# left_revision1_1.net
KiCad netlist of a schematic drawn in EAGLE
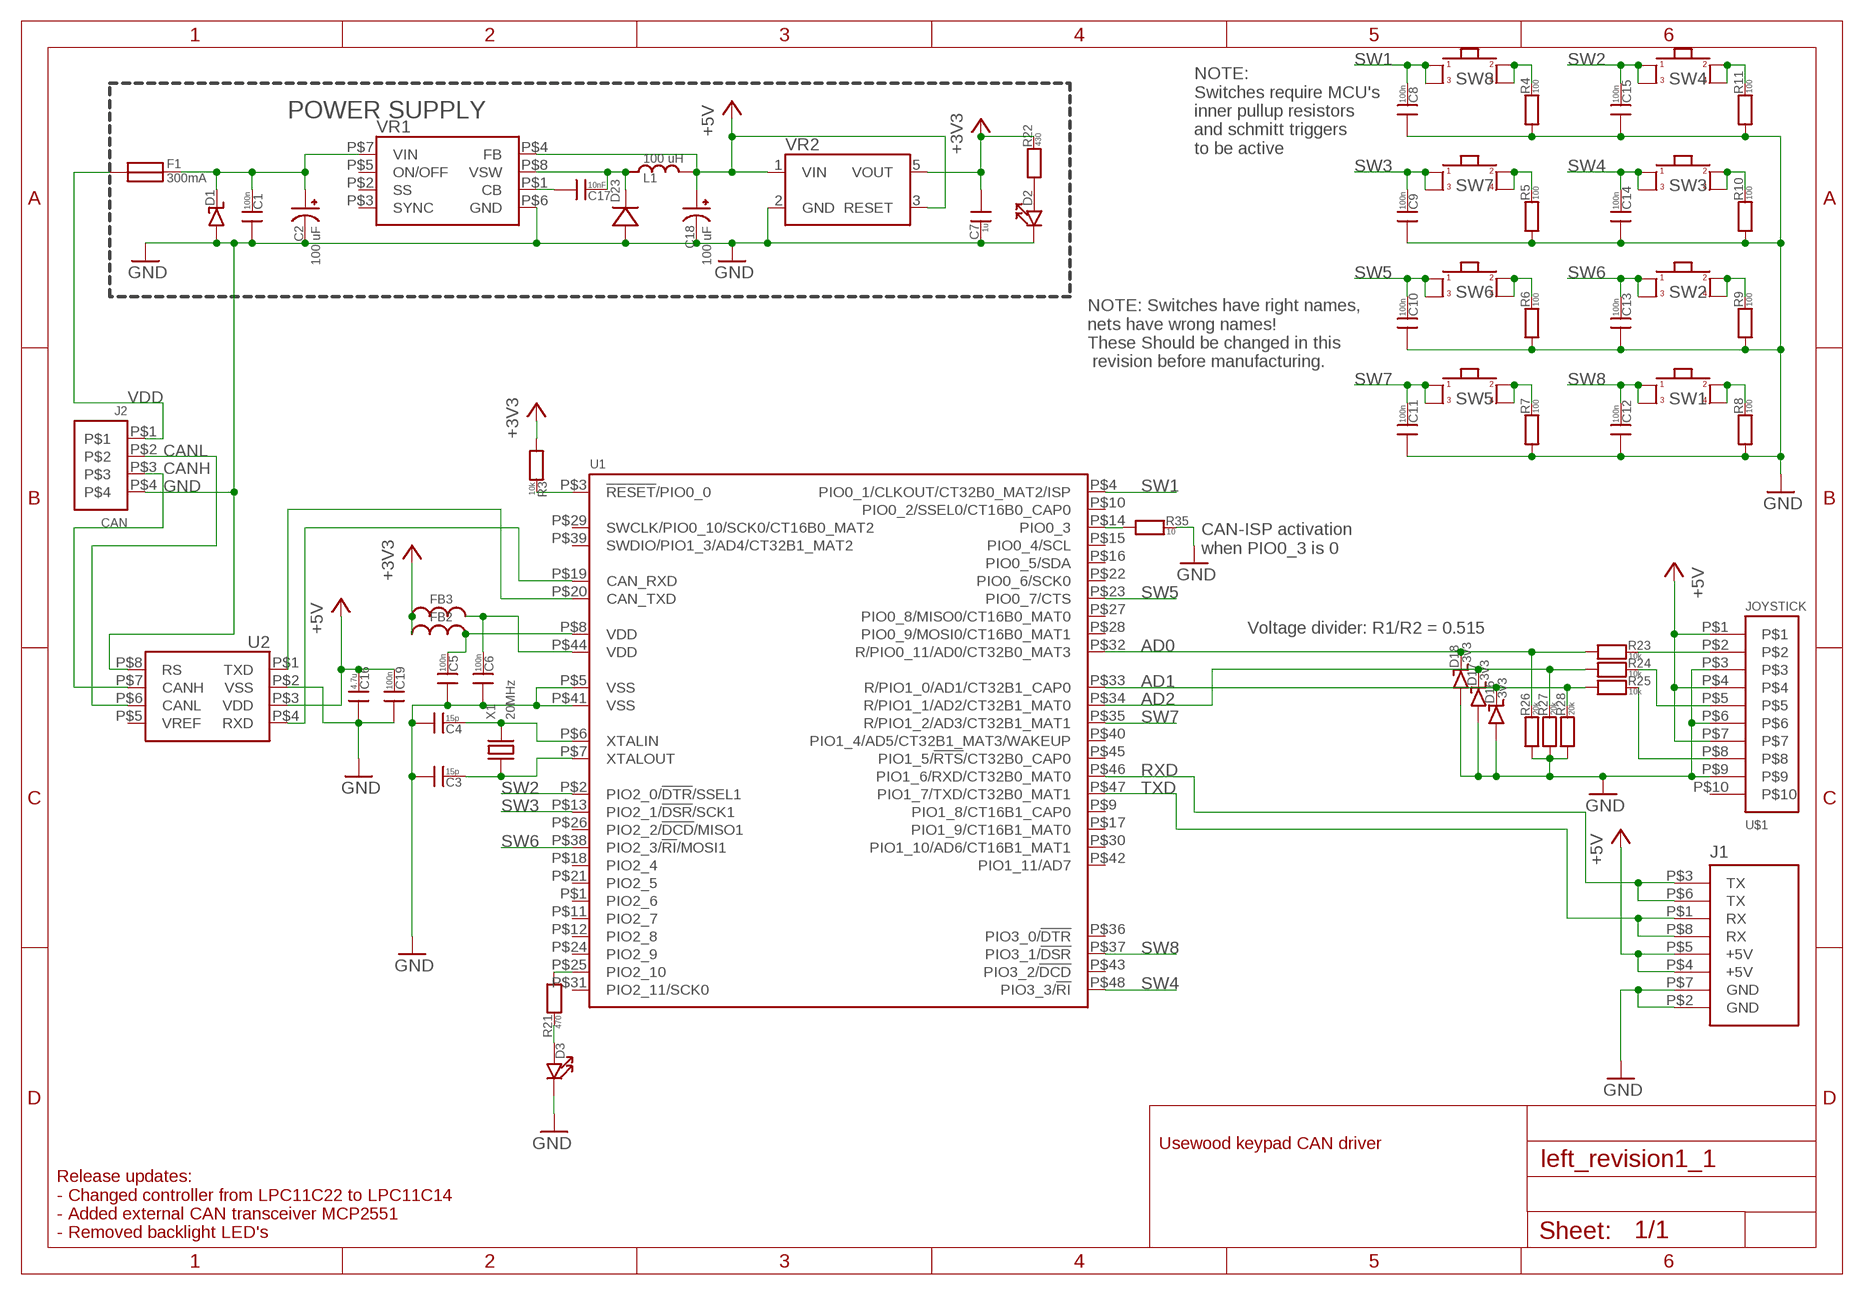
[diagram p0: schematic, sheet 1]

(export (version "E")
  (design (tool "Eeschema 10.0.6"))
  (components
    (comp (ref "C1")
      (value "100n")
      (footprint "eagle-import:0603_SILKSCREEN")
      (libsource (lib "eagle-import") (part "CAP0603_SILKSCREEN"))
    )
    (comp (ref "C2")
      (value "100 uF")
      (footprint "eagle-import:CAP_POL_SMD_10X10X10MM")
      (libsource (lib "eagle-import") (part "CAP_POLSMD_10X10X10MM"))
    )
    (comp (ref "C3")
      (value "15p")
      (footprint "eagle-import:0603_SILKSCREEN")
      (libsource (lib "eagle-import") (part "CAP0603_SILKSCREEN"))
    )
    (comp (ref "C4")
      (value "15p")
      (footprint "eagle-import:0603_SILKSCREEN")
      (libsource (lib "eagle-import") (part "CAP0603_SILKSCREEN"))
    )
    (comp (ref "C5")
      (value "100n")
      (footprint "eagle-import:0603_SILKSCREEN")
      (libsource (lib "eagle-import") (part "CAP0603_SILKSCREEN"))
    )
    (comp (ref "C6")
      (value "100n")
      (footprint "eagle-import:0603_SILKSCREEN")
      (libsource (lib "eagle-import") (part "CAP0603_SILKSCREEN"))
    )
    (comp (ref "C7")
      (value "1u")
      (footprint "eagle-import:0603_SILKSCREEN")
      (libsource (lib "eagle-import") (part "CAP0603_SILKSCREEN"))
    )
    (comp (ref "C8")
      (value "100n")
      (footprint "eagle-import:0603_SILKSCREEN")
      (libsource (lib "eagle-import") (part "CAP0603_SILKSCREEN"))
    )
    (comp (ref "C9")
      (value "100n")
      (footprint "eagle-import:0603_SILKSCREEN")
      (libsource (lib "eagle-import") (part "CAP0603_SILKSCREEN"))
    )
    (comp (ref "C10")
      (value "100n")
      (footprint "eagle-import:0603_SILKSCREEN")
      (libsource (lib "eagle-import") (part "CAP0603_SILKSCREEN"))
    )
    (comp (ref "C11")
      (value "100n")
      (footprint "eagle-import:0603_SILKSCREEN")
      (libsource (lib "eagle-import") (part "CAP0603_SILKSCREEN"))
    )
    (comp (ref "C12")
      (value "100n")
      (footprint "eagle-import:0603_SILKSCREEN")
      (libsource (lib "eagle-import") (part "CAP0603_SILKSCREEN"))
    )
    (comp (ref "C13")
      (value "100n")
      (footprint "eagle-import:0603_SILKSCREEN")
      (libsource (lib "eagle-import") (part "CAP0603_SILKSCREEN"))
    )
    (comp (ref "C14")
      (value "100n")
      (footprint "eagle-import:0603_SILKSCREEN")
      (libsource (lib "eagle-import") (part "CAP0603_SILKSCREEN"))
    )
    (comp (ref "C15")
      (value "100n")
      (footprint "eagle-import:0603_SILKSCREEN")
      (libsource (lib "eagle-import") (part "CAP0603_SILKSCREEN"))
    )
    (comp (ref "C16")
      (value "4.7u")
      (footprint "eagle-import:0603_SILKSCREEN")
      (libsource (lib "eagle-import") (part "CAP0603_SILKSCREEN"))
    )
    (comp (ref "C17")
      (value "10nF")
      (footprint "eagle-import:0603_SILKSCREEN")
      (libsource (lib "eagle-import") (part "CAP0603_SILKSCREEN"))
    )
    (comp (ref "C18")
      (value "100 uF")
      (footprint "eagle-import:CAP_POL_SMD_10X10X10MM")
      (libsource (lib "eagle-import") (part "CAP_POLSMD_10X10X10MM"))
    )
    (comp (ref "C19")
      (value "100n")
      (footprint "eagle-import:0603_SILKSCREEN")
      (libsource (lib "eagle-import") (part "CAP0603_SILKSCREEN"))
    )
    (comp (ref "D1")
      (value "DIODE_TVSDO-214AA")
      (footprint "eagle-import:DO-214AB")
      (libsource (lib "eagle-import") (part "DIODE_TVSDO-214AA"))
    )
    (comp (ref "D2")
      (value "LED0603_SILKSCREEN")
      (footprint "eagle-import:0603_SILKSCREEN")
      (libsource (lib "eagle-import") (part "LED0603_SILKSCREEN"))
    )
    (comp (ref "D3")
      (value "LED0603_SILKSCREEN")
      (footprint "eagle-import:0603_SILKSCREEN")
      (libsource (lib "eagle-import") (part "LED0603_SILKSCREEN"))
    )
    (comp (ref "D16")
      (value "3v3")
      (footprint "eagle-import:SOD123")
      (libsource (lib "eagle-import") (part "DIODE_ZENERSDO123"))
    )
    (comp (ref "D17")
      (value "3v3")
      (footprint "eagle-import:SOD123")
      (libsource (lib "eagle-import") (part "DIODE_ZENERSDO123"))
    )
    (comp (ref "D18")
      (value "3v3")
      (footprint "eagle-import:SOD123")
      (libsource (lib "eagle-import") (part "DIODE_ZENERSDO123"))
    )
    (comp (ref "D23")
      (value "DIODEDO219AB")
      (footprint "eagle-import:DO219AB")
      (libsource (lib "eagle-import") (part "DIODEDO219AB"))
    )
    (comp (ref "F1")
      (value "300mA")
      (footprint "eagle-import:FUSE_100MA")
      (libsource (lib "eagle-import") (part "FUSE100MA"))
    )
    (comp (ref "FB2")
      (value "FERRITE0603_SILKSCREEN")
      (footprint "eagle-import:0603_SILKSCREEN")
      (libsource (lib "eagle-import") (part "FERRITE0603_SILKSCREEN"))
    )
    (comp (ref "FB3")
      (value "FERRITE0603_SILKSCREEN")
      (footprint "eagle-import:0603_SILKSCREEN")
      (libsource (lib "eagle-import") (part "FERRITE0603_SILKSCREEN"))
    )
    (comp (ref "J1")
      (value "HEADER_USART_2_TH")
      (footprint "eagle-import:HEADER_USART_2_TH")
      (libsource (lib "eagle-import") (part "HEADER_USART_2_TH"))
    )
    (comp (ref "J2")
      (value "CAN")
      (footprint "eagle-import:MOLEX_MICRO-FIT_4WAY")
      (libsource (lib "eagle-import") (part "MOLEX_MICRO-FIT_4WAYTH"))
    )
    (comp (ref "L1")
      (value "100 uH")
      (footprint "eagle-import:INDUCTOR_BOURNS_10X13X5MM")
      (libsource (lib "eagle-import") (part "INDUCTORBOURNS_10X13X5MM"))
    )
    (comp (ref "R3")
      (value "10k")
      (footprint "eagle-import:0603_SILKSCREEN")
      (libsource (lib "eagle-import") (part "RES0604_SILKSCREEN"))
    )
    (comp (ref "R4")
      (value "100")
      (footprint "eagle-import:0603_SILKSCREEN")
      (libsource (lib "eagle-import") (part "RES0604_SILKSCREEN"))
    )
    (comp (ref "R5")
      (value "100")
      (footprint "eagle-import:0603_SILKSCREEN")
      (libsource (lib "eagle-import") (part "RES0604_SILKSCREEN"))
    )
    (comp (ref "R6")
      (value "100")
      (footprint "eagle-import:0603_SILKSCREEN")
      (libsource (lib "eagle-import") (part "RES0604_SILKSCREEN"))
    )
    (comp (ref "R7")
      (value "100")
      (footprint "eagle-import:0603_SILKSCREEN")
      (libsource (lib "eagle-import") (part "RES0604_SILKSCREEN"))
    )
    (comp (ref "R8")
      (value "100")
      (footprint "eagle-import:0603_SILKSCREEN")
      (libsource (lib "eagle-import") (part "RES0604_SILKSCREEN"))
    )
    (comp (ref "R9")
      (value "100")
      (footprint "eagle-import:0603_SILKSCREEN")
      (libsource (lib "eagle-import") (part "RES0604_SILKSCREEN"))
    )
    (comp (ref "R10")
      (value "100")
      (footprint "eagle-import:0603_SILKSCREEN")
      (libsource (lib "eagle-import") (part "RES0604_SILKSCREEN"))
    )
    (comp (ref "R11")
      (value "100")
      (footprint "eagle-import:0603_SILKSCREEN")
      (libsource (lib "eagle-import") (part "RES0604_SILKSCREEN"))
    )
    (comp (ref "R21")
      (value "470")
      (footprint "eagle-import:0603_SILKSCREEN")
      (libsource (lib "eagle-import") (part "RES0604_SILKSCREEN"))
    )
    (comp (ref "R22")
      (value "430")
      (footprint "eagle-import:0603_SILKSCREEN")
      (libsource (lib "eagle-import") (part "RES0604_SILKSCREEN"))
    )
    (comp (ref "R23")
      (value "10k")
      (footprint "eagle-import:0603_SILKSCREEN")
      (libsource (lib "eagle-import") (part "RES0604_SILKSCREEN"))
    )
    (comp (ref "R24")
      (value "10k")
      (footprint "eagle-import:0603_SILKSCREEN")
      (libsource (lib "eagle-import") (part "RES0604_SILKSCREEN"))
    )
    (comp (ref "R25")
      (value "10k")
      (footprint "eagle-import:0603_SILKSCREEN")
      (libsource (lib "eagle-import") (part "RES0604_SILKSCREEN"))
    )
    (comp (ref "R26")
      (value "20k")
      (footprint "eagle-import:0603_SILKSCREEN")
      (libsource (lib "eagle-import") (part "RES0604_SILKSCREEN"))
    )
    (comp (ref "R27")
      (value "20k")
      (footprint "eagle-import:0603_SILKSCREEN")
      (libsource (lib "eagle-import") (part "RES0604_SILKSCREEN"))
    )
    (comp (ref "R28")
      (value "20k")
      (footprint "eagle-import:0603_SILKSCREEN")
      (libsource (lib "eagle-import") (part "RES0604_SILKSCREEN"))
    )
    (comp (ref "R35")
      (value "10")
      (footprint "eagle-import:0603_SILKSCREEN")
      (libsource (lib "eagle-import") (part "RES0604_SILKSCREEN"))
    )
    (comp (ref "SW1")
      (value "SWITCH12X12MM_CENTER_HOLE")
      (footprint "eagle-import:SWITCH_12X12MM_CENTER_HOLE")
      (libsource (lib "eagle-import") (part "SWITCH12X12MM_CENTER_HOLE"))
    )
    (comp (ref "SW2")
      (value "SWITCH12X12MM_CENTER_HOLE")
      (footprint "eagle-import:SWITCH_12X12MM_CENTER_HOLE")
      (libsource (lib "eagle-import") (part "SWITCH12X12MM_CENTER_HOLE"))
    )
    (comp (ref "SW3")
      (value "SWITCH12X12MM_CENTER_HOLE")
      (footprint "eagle-import:SWITCH_12X12MM_CENTER_HOLE")
      (libsource (lib "eagle-import") (part "SWITCH12X12MM_CENTER_HOLE"))
    )
    (comp (ref "SW4")
      (value "SWITCH12X12MM_CENTER_HOLE")
      (footprint "eagle-import:SWITCH_12X12MM_CENTER_HOLE")
      (libsource (lib "eagle-import") (part "SWITCH12X12MM_CENTER_HOLE"))
    )
    (comp (ref "SW5")
      (value "SWITCH12X12MM_CENTER_HOLE")
      (footprint "eagle-import:SWITCH_12X12MM_CENTER_HOLE")
      (libsource (lib "eagle-import") (part "SWITCH12X12MM_CENTER_HOLE"))
    )
    (comp (ref "SW6")
      (value "SWITCH12X12MM_CENTER_HOLE")
      (footprint "eagle-import:SWITCH_12X12MM_CENTER_HOLE")
      (libsource (lib "eagle-import") (part "SWITCH12X12MM_CENTER_HOLE"))
    )
    (comp (ref "SW7")
      (value "SWITCH12X12MM_CENTER_HOLE")
      (footprint "eagle-import:SWITCH_12X12MM_CENTER_HOLE")
      (libsource (lib "eagle-import") (part "SWITCH12X12MM_CENTER_HOLE"))
    )
    (comp (ref "SW8")
      (value "SWITCH12X12MM_CENTER_HOLE")
      (footprint "eagle-import:SWITCH_12X12MM_CENTER_HOLE")
      (libsource (lib "eagle-import") (part "SWITCH12X12MM_CENTER_HOLE"))
    )
    (comp (ref "U$1")
      (value "JOYSTICK")
      (footprint "eagle-import:MOLEX-MICRO-FIT_10WAY")
      (libsource (lib "eagle-import") (part "MOLEX_MICRO-FIT_10WAYTH"))
    )
    (comp (ref "U1")
      (value "LPC11C14_QFP48")
      (footprint "eagle-import:QFP48")
      (libsource (lib "eagle-import") (part "LPC11C14_QFP48"))
    )
    (comp (ref "U2")
      (value "MCP2551_SOIC8")
      (footprint "eagle-import:SOIC8")
      (libsource (lib "eagle-import") (part "MCP2551_SOIC8"))
    )
    (comp (ref "VR1")
      (value "LM2671SOIC8")
      (footprint "eagle-import:SOIC8")
      (libsource (lib "eagle-import") (part "LM2671SOIC8"))
    )
    (comp (ref "VR2")
      (value "LP2985SOP5")
      (footprint "eagle-import:SOP5")
      (libsource (lib "eagle-import") (part "LP2985SOP5"))
    )
    (comp (ref "X1")
      (value "20MHz")
      (footprint "eagle-import:XTAL_SMD_5X3.2")
      (libsource (lib "eagle-import") (part "XTALSMD_5X3.2"))
    )
  )
  (nets
    (net (code "1") (name "+3V3") (class "Default")
      (node (ref "C7") (pin "0") (pinfunction "P$1_0") (pintype "bidirectional"))
      (node (ref "FB2") (pin "0") (pinfunction "P$1_0") (pintype "bidirectional"))
      (node (ref "FB3") (pin "0") (pinfunction "P$1_0") (pintype "bidirectional"))
      (node (ref "R22") (pin "1") (pinfunction "P$2_1") (pintype "bidirectional"))
      (node (ref "R3") (pin "0") (pinfunction "P$1_0") (pintype "bidirectional"))
      (node (ref "VR2") (pin "5") (pinfunction "VOUT_5") (pintype "bidirectional"))
    )
    (net (code "2") (name "+5V") (class "Default")
      (node (ref "C16") (pin "1") (pinfunction "P$2_1") (pintype "bidirectional"))
      (node (ref "C18") (pin "+") (pinfunction "+_+") (pintype "bidirectional"))
      (node (ref "C19") (pin "1") (pinfunction "P$2_1") (pintype "bidirectional"))
      (node (ref "J1") (pin "P$4") (pinfunction "+5V_P$4") (pintype "bidirectional"))
      (node (ref "J1") (pin "P$5") (pinfunction "+5V_P$5") (pintype "bidirectional"))
      (node (ref "L1") (pin "P$2") (pinfunction "P$2_P$2") (pintype "bidirectional"))
      (node (ref "U$1") (pin "P$1") (pinfunction "P$1_P$1") (pintype "bidirectional"))
      (node (ref "U$1") (pin "P$4") (pinfunction "P$4_P$4") (pintype "bidirectional"))
      (node (ref "U$1") (pin "P$7") (pinfunction "P$7_P$7") (pintype "bidirectional"))
      (node (ref "U2") (pin "P$3") (pinfunction "VDD_P$3") (pintype "bidirectional"))
      (node (ref "VR1") (pin "P$4") (pinfunction "FB_P$4") (pintype "bidirectional"))
      (node (ref "VR2") (pin "1") (pinfunction "VIN_1") (pintype "bidirectional"))
      (node (ref "VR2") (pin "3") (pinfunction "RESET_3") (pintype "bidirectional"))
    )
    (net (code "3") (name "/AD0") (class "Default")
      (node (ref "D18") (pin "P$2") (pinfunction "N_P$2") (pintype "bidirectional"))
      (node (ref "R23") (pin "0") (pinfunction "P$1_0") (pintype "bidirectional"))
      (node (ref "R26") (pin "1") (pinfunction "P$2_1") (pintype "bidirectional"))
      (node (ref "U1") (pin "P$32") (pinfunction "R/PIO0_11/AD0/CT32B0_MAT3_P$32") (pintype "bidirectional"))
    )
    (net (code "4") (name "/AD1") (class "Default")
      (node (ref "D16") (pin "P$2") (pinfunction "N_P$2") (pintype "bidirectional"))
      (node (ref "R25") (pin "0") (pinfunction "P$1_0") (pintype "bidirectional"))
      (node (ref "R28") (pin "1") (pinfunction "P$2_1") (pintype "bidirectional"))
      (node (ref "U1") (pin "P$33") (pinfunction "R/PIO1_0/AD1/CT32B1_CAP0_P$33") (pintype "bidirectional"))
    )
    (net (code "5") (name "/AD2") (class "Default")
      (node (ref "D17") (pin "P$2") (pinfunction "N_P$2") (pintype "bidirectional"))
      (node (ref "R24") (pin "0") (pinfunction "P$1_0") (pintype "bidirectional"))
      (node (ref "R27") (pin "1") (pinfunction "P$2_1") (pintype "bidirectional"))
      (node (ref "U1") (pin "P$34") (pinfunction "R/PIO1_1/AD2/CT32B1_MAT0_P$34") (pintype "bidirectional"))
    )
    (net (code "6") (name "/CANH") (class "Default")
      (node (ref "J2") (pin "P$3") (pinfunction "P$3_P$3") (pintype "bidirectional"))
      (node (ref "U2") (pin "P$7") (pinfunction "CANH_P$7") (pintype "bidirectional"))
    )
    (net (code "7") (name "/CANL") (class "Default")
      (node (ref "J2") (pin "P$2") (pinfunction "P$2_P$2") (pintype "bidirectional"))
      (node (ref "U2") (pin "P$6") (pinfunction "CANL_P$6") (pintype "bidirectional"))
    )
    (net (code "8") (name "/RXD") (class "Default")
      (node (ref "J1") (pin "P$3") (pinfunction "TX_P$3") (pintype "bidirectional"))
      (node (ref "J1") (pin "P$6") (pinfunction "TX_P$6") (pintype "bidirectional"))
      (node (ref "U1") (pin "P$46") (pinfunction "PIO1_6/RXD/CT32B0_MAT0_P$46") (pintype "bidirectional"))
    )
    (net (code "9") (name "/SW1") (class "Default")
      (node (ref "C8") (pin "1") (pinfunction "P$2_1") (pintype "bidirectional"))
      (node (ref "SW8") (pin "P$1") (pinfunction "P$1_P$1") (pintype "bidirectional"))
      (node (ref "SW8") (pin "P$2") (pinfunction "P$3_P$2") (pintype "bidirectional"))
      (node (ref "U1") (pin "P$4") (pinfunction "PIO0_1/CLKOUT/CT32B0_MAT2/ISP_P$4") (pintype "bidirectional"))
    )
    (net (code "10") (name "/SW2") (class "Default")
      (node (ref "C15") (pin "1") (pinfunction "P$2_1") (pintype "bidirectional"))
      (node (ref "SW4") (pin "P$1") (pinfunction "P$1_P$1") (pintype "bidirectional"))
      (node (ref "SW4") (pin "P$2") (pinfunction "P$3_P$2") (pintype "bidirectional"))
      (node (ref "U1") (pin "P$2") (pinfunction "PIO2_0/~{DTR}/SSEL1_P$2") (pintype "bidirectional"))
    )
    (net (code "11") (name "/SW3") (class "Default")
      (node (ref "C9") (pin "1") (pinfunction "P$2_1") (pintype "bidirectional"))
      (node (ref "SW7") (pin "P$1") (pinfunction "P$1_P$1") (pintype "bidirectional"))
      (node (ref "SW7") (pin "P$2") (pinfunction "P$3_P$2") (pintype "bidirectional"))
      (node (ref "U1") (pin "P$13") (pinfunction "PIO2_1/~{DSR}/SCK1_P$13") (pintype "bidirectional"))
    )
    (net (code "12") (name "/SW4") (class "Default")
      (node (ref "C14") (pin "1") (pinfunction "P$2_1") (pintype "bidirectional"))
      (node (ref "SW3") (pin "P$1") (pinfunction "P$1_P$1") (pintype "bidirectional"))
      (node (ref "SW3") (pin "P$2") (pinfunction "P$3_P$2") (pintype "bidirectional"))
      (node (ref "U1") (pin "P$48") (pinfunction "PIO3_3/~{RI}_P$48") (pintype "bidirectional"))
    )
    (net (code "13") (name "/SW5") (class "Default")
      (node (ref "C10") (pin "1") (pinfunction "P$2_1") (pintype "bidirectional"))
      (node (ref "SW6") (pin "P$1") (pinfunction "P$1_P$1") (pintype "bidirectional"))
      (node (ref "SW6") (pin "P$2") (pinfunction "P$3_P$2") (pintype "bidirectional"))
      (node (ref "U1") (pin "P$23") (pinfunction "PIO0_7/CTS_P$23") (pintype "bidirectional"))
    )
    (net (code "14") (name "/SW6") (class "Default")
      (node (ref "C13") (pin "1") (pinfunction "P$2_1") (pintype "bidirectional"))
      (node (ref "SW2") (pin "P$1") (pinfunction "P$1_P$1") (pintype "bidirectional"))
      (node (ref "SW2") (pin "P$2") (pinfunction "P$3_P$2") (pintype "bidirectional"))
      (node (ref "U1") (pin "P$38") (pinfunction "PIO2_3/~{RI}/MOSI1_P$38") (pintype "bidirectional"))
    )
    (net (code "15") (name "/SW7") (class "Default")
      (node (ref "C11") (pin "1") (pinfunction "P$2_1") (pintype "bidirectional"))
      (node (ref "SW5") (pin "P$1") (pinfunction "P$1_P$1") (pintype "bidirectional"))
      (node (ref "SW5") (pin "P$2") (pinfunction "P$3_P$2") (pintype "bidirectional"))
      (node (ref "U1") (pin "P$35") (pinfunction "R/PIO1_2/AD3/CT32B1_MAT1_P$35") (pintype "bidirectional"))
    )
    (net (code "16") (name "/SW8") (class "Default")
      (node (ref "C12") (pin "1") (pinfunction "P$2_1") (pintype "bidirectional"))
      (node (ref "SW1") (pin "P$1") (pinfunction "P$1_P$1") (pintype "bidirectional"))
      (node (ref "SW1") (pin "P$2") (pinfunction "P$3_P$2") (pintype "bidirectional"))
      (node (ref "U1") (pin "P$37") (pinfunction "PIO3_1/~{DSR}_P$37") (pintype "bidirectional"))
    )
    (net (code "17") (name "/TXD") (class "Default")
      (node (ref "J1") (pin "P$1") (pinfunction "RX_P$1") (pintype "bidirectional"))
      (node (ref "J1") (pin "P$8") (pinfunction "RX_P$8") (pintype "bidirectional"))
      (node (ref "U1") (pin "P$47") (pinfunction "PIO1_7/TXD/CT32B0_MAT1_P$47") (pintype "bidirectional"))
    )
    (net (code "18") (name "/VDD") (class "Default")
      (node (ref "F1") (pin "P$1") (pinfunction "P$1_P$1") (pintype "bidirectional"))
      (node (ref "J2") (pin "P$1") (pinfunction "P$1_P$1") (pintype "bidirectional"))
    )
    (net (code "19") (name "GND") (class "Default")
      (node (ref "C1") (pin "0") (pinfunction "P$1_0") (pintype "bidirectional"))
      (node (ref "C10") (pin "0") (pinfunction "P$1_0") (pintype "bidirectional"))
      (node (ref "C11") (pin "0") (pinfunction "P$1_0") (pintype "bidirectional"))
      (node (ref "C12") (pin "0") (pinfunction "P$1_0") (pintype "bidirectional"))
      (node (ref "C13") (pin "0") (pinfunction "P$1_0") (pintype "bidirectional"))
      (node (ref "C14") (pin "0") (pinfunction "P$1_0") (pintype "bidirectional"))
      (node (ref "C15") (pin "0") (pinfunction "P$1_0") (pintype "bidirectional"))
      (node (ref "C16") (pin "0") (pinfunction "P$1_0") (pintype "bidirectional"))
      (node (ref "C18") (pin "-") (pinfunction "-_-") (pintype "bidirectional"))
      (node (ref "C19") (pin "0") (pinfunction "P$1_0") (pintype "bidirectional"))
      (node (ref "C2") (pin "-") (pinfunction "-_-") (pintype "bidirectional"))
      (node (ref "C3") (pin "0") (pinfunction "P$1_0") (pintype "bidirectional"))
      (node (ref "C4") (pin "0") (pinfunction "P$1_0") (pintype "bidirectional"))
      (node (ref "C5") (pin "0") (pinfunction "P$1_0") (pintype "bidirectional"))
      (node (ref "C6") (pin "0") (pinfunction "P$1_0") (pintype "bidirectional"))
      (node (ref "C7") (pin "1") (pinfunction "P$2_1") (pintype "bidirectional"))
      (node (ref "C8") (pin "0") (pinfunction "P$1_0") (pintype "bidirectional"))
      (node (ref "C9") (pin "0") (pinfunction "P$1_0") (pintype "bidirectional"))
      (node (ref "D1") (pin "P$1") (pinfunction "P_P$1") (pintype "bidirectional"))
      (node (ref "D16") (pin "P$1") (pinfunction "P_P$1") (pintype "bidirectional"))
      (node (ref "D17") (pin "P$1") (pinfunction "P_P$1") (pintype "bidirectional"))
      (node (ref "D18") (pin "P$1") (pinfunction "P_P$1") (pintype "bidirectional"))
      (node (ref "D2") (pin "1") (pinfunction "1_1") (pintype "bidirectional"))
      (node (ref "D23") (pin "P$1") (pinfunction "P_P$1") (pintype "bidirectional"))
      (node (ref "D3") (pin "1") (pinfunction "1_1") (pintype "bidirectional"))
      (node (ref "J1") (pin "P$2") (pinfunction "GND_P$2") (pintype "bidirectional"))
      (node (ref "J1") (pin "P$7") (pinfunction "GND_P$7") (pintype "bidirectional"))
      (node (ref "J2") (pin "P$4") (pinfunction "P$4_P$4") (pintype "bidirectional"))
      (node (ref "R10") (pin "0") (pinfunction "P$1_0") (pintype "bidirectional"))
      (node (ref "R11") (pin "0") (pinfunction "P$1_0") (pintype "bidirectional"))
      (node (ref "R26") (pin "0") (pinfunction "P$1_0") (pintype "bidirectional"))
      (node (ref "R27") (pin "0") (pinfunction "P$1_0") (pintype "bidirectional"))
      (node (ref "R28") (pin "0") (pinfunction "P$1_0") (pintype "bidirectional"))
      (node (ref "R35") (pin "1") (pinfunction "P$2_1") (pintype "bidirectional"))
      (node (ref "R4") (pin "0") (pinfunction "P$1_0") (pintype "bidirectional"))
      (node (ref "R5") (pin "0") (pinfunction "P$1_0") (pintype "bidirectional"))
      (node (ref "R6") (pin "0") (pinfunction "P$1_0") (pintype "bidirectional"))
      (node (ref "R7") (pin "0") (pinfunction "P$1_0") (pintype "bidirectional"))
      (node (ref "R8") (pin "0") (pinfunction "P$1_0") (pintype "bidirectional"))
      (node (ref "R9") (pin "0") (pinfunction "P$1_0") (pintype "bidirectional"))
      (node (ref "U$1") (pin "P$3") (pinfunction "P$3_P$3") (pintype "bidirectional"))
      (node (ref "U$1") (pin "P$6") (pinfunction "P$6_P$6") (pintype "bidirectional"))
      (node (ref "U$1") (pin "P$9") (pinfunction "P$9_P$9") (pintype "bidirectional"))
      (node (ref "U1") (pin "P$41") (pinfunction "VSS_P$41") (pintype "bidirectional"))
      (node (ref "U1") (pin "P$5") (pinfunction "VSS_P$5") (pintype "bidirectional"))
      (node (ref "U2") (pin "P$2") (pinfunction "VSS_P$2") (pintype "bidirectional"))
      (node (ref "U2") (pin "P$8") (pinfunction "RS_P$8") (pintype "bidirectional"))
      (node (ref "VR1") (pin "P$6") (pinfunction "GND_P$6") (pintype "bidirectional"))
      (node (ref "VR2") (pin "2") (pinfunction "GND_2") (pintype "bidirectional"))
    )
    (net (code "20") (name "Net-(C1-P$2)") (class "Default")
      (node (ref "C1") (pin "1") (pinfunction "P$2_1") (pintype "bidirectional"))
      (node (ref "C2") (pin "+") (pinfunction "+_+") (pintype "bidirectional"))
      (node (ref "D1") (pin "P$2") (pinfunction "N_P$2") (pintype "bidirectional"))
      (node (ref "F1") (pin "P$2") (pinfunction "P$2_P$2") (pintype "bidirectional"))
      (node (ref "VR1") (pin "P$7") (pinfunction "VIN_P$7") (pintype "bidirectional"))
    )
    (net (code "21") (name "Net-(C3-P$2)") (class "Default")
      (node (ref "C3") (pin "1") (pinfunction "P$2_1") (pintype "bidirectional"))
      (node (ref "U1") (pin "P$7") (pinfunction "XTALOUT_P$7") (pintype "bidirectional"))
      (node (ref "X1") (pin "P$1") (pinfunction "P$1_P$1") (pintype "bidirectional"))
    )
    (net (code "22") (name "Net-(C4-P$2)") (class "Default")
      (node (ref "C4") (pin "1") (pinfunction "P$2_1") (pintype "bidirectional"))
      (node (ref "U1") (pin "P$6") (pinfunction "XTALIN_P$6") (pintype "bidirectional"))
      (node (ref "X1") (pin "P$2") (pinfunction "P$2_P$2") (pintype "bidirectional"))
    )
    (net (code "23") (name "Net-(C5-P$2)") (class "Default")
      (node (ref "C5") (pin "1") (pinfunction "P$2_1") (pintype "bidirectional"))
      (node (ref "FB2") (pin "1") (pinfunction "P$2_1") (pintype "bidirectional"))
      (node (ref "U1") (pin "P$8") (pinfunction "VDD_P$8") (pintype "bidirectional"))
    )
    (net (code "24") (name "Net-(C6-P$2)") (class "Default")
      (node (ref "C6") (pin "1") (pinfunction "P$2_1") (pintype "bidirectional"))
      (node (ref "FB3") (pin "1") (pinfunction "P$2_1") (pintype "bidirectional"))
      (node (ref "U1") (pin "P$44") (pinfunction "VDD_P$44") (pintype "bidirectional"))
    )
    (net (code "25") (name "Net-(C17-P$1)") (class "Default")
      (node (ref "C17") (pin "0") (pinfunction "P$1_0") (pintype "bidirectional"))
      (node (ref "VR1") (pin "P$1") (pinfunction "CB_P$1") (pintype "bidirectional"))
    )
    (net (code "26") (name "Net-(C17-P$2)") (class "Default")
      (node (ref "C17") (pin "1") (pinfunction "P$2_1") (pintype "bidirectional"))
      (node (ref "D23") (pin "P$2") (pinfunction "N_P$2") (pintype "bidirectional"))
      (node (ref "L1") (pin "P$1") (pinfunction "P$1_P$1") (pintype "bidirectional"))
      (node (ref "VR1") (pin "P$8") (pinfunction "VSW_P$8") (pintype "bidirectional"))
    )
    (net (code "27") (name "Net-(R3-P$2)") (class "Default")
      (node (ref "R3") (pin "1") (pinfunction "P$2_1") (pintype "bidirectional"))
      (node (ref "U1") (pin "P$3") (pinfunction "~{RESET}/PIO0_0_P$3") (pintype "bidirectional"))
    )
    (net (code "28") (name "Net-(R4-P$2)") (class "Default")
      (node (ref "R4") (pin "1") (pinfunction "P$2_1") (pintype "bidirectional"))
      (node (ref "SW8") (pin "P$3") (pinfunction "P$2_P$3") (pintype "bidirectional"))
      (node (ref "SW8") (pin "P$4") (pinfunction "P$4_P$4") (pintype "bidirectional"))
    )
    (net (code "29") (name "Net-(R5-P$2)") (class "Default")
      (node (ref "R5") (pin "1") (pinfunction "P$2_1") (pintype "bidirectional"))
      (node (ref "SW7") (pin "P$3") (pinfunction "P$2_P$3") (pintype "bidirectional"))
      (node (ref "SW7") (pin "P$4") (pinfunction "P$4_P$4") (pintype "bidirectional"))
    )
    (net (code "30") (name "Net-(R6-P$2)") (class "Default")
      (node (ref "R6") (pin "1") (pinfunction "P$2_1") (pintype "bidirectional"))
      (node (ref "SW6") (pin "P$3") (pinfunction "P$2_P$3") (pintype "bidirectional"))
      (node (ref "SW6") (pin "P$4") (pinfunction "P$4_P$4") (pintype "bidirectional"))
    )
    (net (code "31") (name "Net-(R7-P$2)") (class "Default")
      (node (ref "R7") (pin "1") (pinfunction "P$2_1") (pintype "bidirectional"))
      (node (ref "SW5") (pin "P$3") (pinfunction "P$2_P$3") (pintype "bidirectional"))
      (node (ref "SW5") (pin "P$4") (pinfunction "P$4_P$4") (pintype "bidirectional"))
    )
    (net (code "32") (name "Net-(R8-P$2)") (class "Default")
      (node (ref "R8") (pin "1") (pinfunction "P$2_1") (pintype "bidirectional"))
      (node (ref "SW1") (pin "P$3") (pinfunction "P$2_P$3") (pintype "bidirectional"))
      (node (ref "SW1") (pin "P$4") (pinfunction "P$4_P$4") (pintype "bidirectional"))
    )
    (net (code "33") (name "Net-(R9-P$2)") (class "Default")
      (node (ref "R9") (pin "1") (pinfunction "P$2_1") (pintype "bidirectional"))
      (node (ref "SW2") (pin "P$3") (pinfunction "P$2_P$3") (pintype "bidirectional"))
      (node (ref "SW2") (pin "P$4") (pinfunction "P$4_P$4") (pintype "bidirectional"))
    )
    (net (code "34") (name "Net-(R10-P$2)") (class "Default")
      (node (ref "R10") (pin "1") (pinfunction "P$2_1") (pintype "bidirectional"))
      (node (ref "SW3") (pin "P$3") (pinfunction "P$2_P$3") (pintype "bidirectional"))
      (node (ref "SW3") (pin "P$4") (pinfunction "P$4_P$4") (pintype "bidirectional"))
    )
    (net (code "35") (name "Net-(R11-P$2)") (class "Default")
      (node (ref "R11") (pin "1") (pinfunction "P$2_1") (pintype "bidirectional"))
      (node (ref "SW4") (pin "P$3") (pinfunction "P$2_P$3") (pintype "bidirectional"))
      (node (ref "SW4") (pin "P$4") (pinfunction "P$4_P$4") (pintype "bidirectional"))
    )
    (net (code "36") (name "Net-(R21-P$1)") (class "Default")
      (node (ref "R21") (pin "0") (pinfunction "P$1_0") (pintype "bidirectional"))
      (node (ref "U1") (pin "P$25") (pinfunction "PIO2_10_P$25") (pintype "bidirectional"))
    )
    (net (code "37") (name "Net-(R21-P$2)") (class "Default")
      (node (ref "D3") (pin "0") (pinfunction "0_0") (pintype "bidirectional"))
      (node (ref "R21") (pin "1") (pinfunction "P$2_1") (pintype "bidirectional"))
    )
    (net (code "38") (name "Net-(R22-P$1)") (class "Default")
      (node (ref "D2") (pin "0") (pinfunction "0_0") (pintype "bidirectional"))
      (node (ref "R22") (pin "0") (pinfunction "P$1_0") (pintype "bidirectional"))
    )
    (net (code "39") (name "Net-(R23-P$2)") (class "Default")
      (node (ref "R23") (pin "1") (pinfunction "P$2_1") (pintype "bidirectional"))
      (node (ref "U$1") (pin "P$2") (pinfunction "P$2_P$2") (pintype "bidirectional"))
    )
    (net (code "40") (name "Net-(R24-P$2)") (class "Default")
      (node (ref "R24") (pin "1") (pinfunction "P$2_1") (pintype "bidirectional"))
      (node (ref "U$1") (pin "P$5") (pinfunction "P$5_P$5") (pintype "bidirectional"))
    )
    (net (code "41") (name "Net-(R25-P$2)") (class "Default")
      (node (ref "R25") (pin "1") (pinfunction "P$2_1") (pintype "bidirectional"))
      (node (ref "U$1") (pin "P$8") (pinfunction "P$8_P$8") (pintype "bidirectional"))
    )
    (net (code "42") (name "Net-(R35-P$1)") (class "Default")
      (node (ref "R35") (pin "0") (pinfunction "P$1_0") (pintype "bidirectional"))
      (node (ref "U1") (pin "P$14") (pinfunction "PIO0_3_P$14") (pintype "bidirectional"))
    )
    (net (code "43") (name "Net-(U1-CAN_RXD)") (class "Default")
      (node (ref "U1") (pin "P$19") (pinfunction "CAN_RXD_P$19") (pintype "bidirectional"))
      (node (ref "U2") (pin "P$4") (pinfunction "RXD_P$4") (pintype "bidirectional"))
    )
    (net (code "44") (name "Net-(U1-CAN_TXD)") (class "Default")
      (node (ref "U1") (pin "P$20") (pinfunction "CAN_TXD_P$20") (pintype "bidirectional"))
      (node (ref "U2") (pin "P$1") (pinfunction "TXD_P$1") (pintype "bidirectional"))
    )
    (net (code "45") (name "unconnected-(U$1-PadP$10)") (class "Default")
      (node (ref "U$1") (pin "P$10") (pinfunction "P$10_P$10") (pintype "bidirectional"))
    )
    (net (code "46") (name "unconnected-(U1-PIO0_2{slash}SSEL0{slash}CT16B0_CAP0-PadP$10)") (class "Default")
      (node (ref "U1") (pin "P$10") (pinfunction "PIO0_2/SSEL0/CT16B0_CAP0_P$10") (pintype "bidirectional"))
    )
    (net (code "47") (name "unconnected-(U1-PIO0_4{slash}SCL-PadP$15)") (class "Default")
      (node (ref "U1") (pin "P$15") (pinfunction "PIO0_4/SCL_P$15") (pintype "bidirectional"))
    )
    (net (code "48") (name "unconnected-(U1-PIO0_5{slash}SDA-PadP$16)") (class "Default")
      (node (ref "U1") (pin "P$16") (pinfunction "PIO0_5/SDA_P$16") (pintype "bidirectional"))
    )
    (net (code "49") (name "unconnected-(U1-PIO0_6{slash}SCK0-PadP$22)") (class "Default")
      (node (ref "U1") (pin "P$22") (pinfunction "PIO0_6/SCK0_P$22") (pintype "bidirectional"))
    )
    (net (code "50") (name "unconnected-(U1-PIO0_8{slash}MISO0{slash}CT16B0_MAT0-PadP$27)") (class "Default")
      (node (ref "U1") (pin "P$27") (pinfunction "PIO0_8/MISO0/CT16B0_MAT0_P$27") (pintype "bidirectional"))
    )
    (net (code "51") (name "unconnected-(U1-PIO0_9{slash}MOSI0{slash}CT16B0_MAT1-PadP$28)") (class "Default")
      (node (ref "U1") (pin "P$28") (pinfunction "PIO0_9/MOSI0/CT16B0_MAT1_P$28") (pintype "bidirectional"))
    )
    (net (code "52") (name "unconnected-(U1-PIO1_4{slash}AD5{slash}CT32B1_MAT3{slash}WAKEUP-PadP$40)") (class "Default")
      (node (ref "U1") (pin "P$40") (pinfunction "PIO1_4/AD5/CT32B1_MAT3/WAKEUP_P$40") (pintype "bidirectional"))
    )
    (net (code "53") (name "unconnected-(U1-PIO1_5{slash}~{RTS}{slash}CT32B0_CAP0-PadP$45)") (class "Default")
      (node (ref "U1") (pin "P$45") (pinfunction "PIO1_5/~{RTS}/CT32B0_CAP0_P$45") (pintype "bidirectional"))
    )
    (net (code "54") (name "unconnected-(U1-PIO1_8{slash}CT16B1_CAP0-PadP$9)") (class "Default")
      (node (ref "U1") (pin "P$9") (pinfunction "PIO1_8/CT16B1_CAP0_P$9") (pintype "bidirectional"))
    )
    (net (code "55") (name "unconnected-(U1-PIO1_9{slash}CT16B1_MAT0-PadP$17)") (class "Default")
      (node (ref "U1") (pin "P$17") (pinfunction "PIO1_9/CT16B1_MAT0_P$17") (pintype "bidirectional"))
    )
    (net (code "56") (name "unconnected-(U1-PIO1_10{slash}AD6{slash}CT16B1_MAT1-PadP$30)") (class "Default")
      (node (ref "U1") (pin "P$30") (pinfunction "PIO1_10/AD6/CT16B1_MAT1_P$30") (pintype "bidirectional"))
    )
    (net (code "57") (name "unconnected-(U1-PIO1_11{slash}AD7-PadP$42)") (class "Default")
      (node (ref "U1") (pin "P$42") (pinfunction "PIO1_11/AD7_P$42") (pintype "bidirectional"))
    )
    (net (code "58") (name "unconnected-(U1-PIO2_2{slash}~{DCD}{slash}MISO1-PadP$26)") (class "Default")
      (node (ref "U1") (pin "P$26") (pinfunction "PIO2_2/~{DCD}/MISO1_P$26") (pintype "bidirectional"))
    )
    (net (code "59") (name "unconnected-(U1-PIO2_4-PadP$18)") (class "Default")
      (node (ref "U1") (pin "P$18") (pinfunction "PIO2_4_P$18") (pintype "bidirectional"))
    )
    (net (code "60") (name "unconnected-(U1-PIO2_5-PadP$21)") (class "Default")
      (node (ref "U1") (pin "P$21") (pinfunction "PIO2_5_P$21") (pintype "bidirectional"))
    )
    (net (code "61") (name "unconnected-(U1-PIO2_6-PadP$1)") (class "Default")
      (node (ref "U1") (pin "P$1") (pinfunction "PIO2_6_P$1") (pintype "bidirectional"))
    )
    (net (code "62") (name "unconnected-(U1-PIO2_7-PadP$11)") (class "Default")
      (node (ref "U1") (pin "P$11") (pinfunction "PIO2_7_P$11") (pintype "bidirectional"))
    )
    (net (code "63") (name "unconnected-(U1-PIO2_8-PadP$12)") (class "Default")
      (node (ref "U1") (pin "P$12") (pinfunction "PIO2_8_P$12") (pintype "bidirectional"))
    )
    (net (code "64") (name "unconnected-(U1-PIO2_9-PadP$24)") (class "Default")
      (node (ref "U1") (pin "P$24") (pinfunction "PIO2_9_P$24") (pintype "bidirectional"))
    )
    (net (code "65") (name "unconnected-(U1-PIO2_11{slash}SCK0-PadP$31)") (class "Default")
      (node (ref "U1") (pin "P$31") (pinfunction "PIO2_11/SCK0_P$31") (pintype "bidirectional"))
    )
    (net (code "66") (name "unconnected-(U1-PIO3_0{slash}~{DTR}-PadP$36)") (class "Default")
      (node (ref "U1") (pin "P$36") (pinfunction "PIO3_0/~{DTR}_P$36") (pintype "bidirectional"))
    )
    (net (code "67") (name "unconnected-(U1-PIO3_2{slash}~{DCD}-PadP$43)") (class "Default")
      (node (ref "U1") (pin "P$43") (pinfunction "PIO3_2/~{DCD}_P$43") (pintype "bidirectional"))
    )
    (net (code "68") (name "unconnected-(U1-SWCLK{slash}PIO0_10{slash}SCK0{slash}CT16B0_MAT2-PadP$29)") (class "Default")
      (node (ref "U1") (pin "P$29") (pinfunction "SWCLK/PIO0_10/SCK0/CT16B0_MAT2_P$29") (pintype "bidirectional"))
    )
    (net (code "69") (name "unconnected-(U1-SWDIO{slash}PIO1_3{slash}AD4{slash}CT32B1_MAT2-PadP$39)") (class "Default")
      (node (ref "U1") (pin "P$39") (pinfunction "SWDIO/PIO1_3/AD4/CT32B1_MAT2_P$39") (pintype "bidirectional"))
    )
    (net (code "70") (name "unconnected-(U2-VREF-PadP$5)") (class "Default")
      (node (ref "U2") (pin "P$5") (pinfunction "VREF_P$5") (pintype "bidirectional"))
    )
    (net (code "71") (name "unconnected-(VR1-ON{slash}OFF-PadP$5)") (class "Default")
      (node (ref "VR1") (pin "P$5") (pinfunction "ON/OFF_P$5") (pintype "bidirectional"))
    )
    (net (code "72") (name "unconnected-(VR1-SS-PadP$2)") (class "Default")
      (node (ref "VR1") (pin "P$2") (pinfunction "SS_P$2") (pintype "bidirectional"))
    )
    (net (code "73") (name "unconnected-(VR1-SYNC-PadP$3)") (class "Default")
      (node (ref "VR1") (pin "P$3") (pinfunction "SYNC_P$3") (pintype "bidirectional"))
    )
  )
)
